# power_supply.net
KiCad netlist of a schematic drawn in Altium Designer
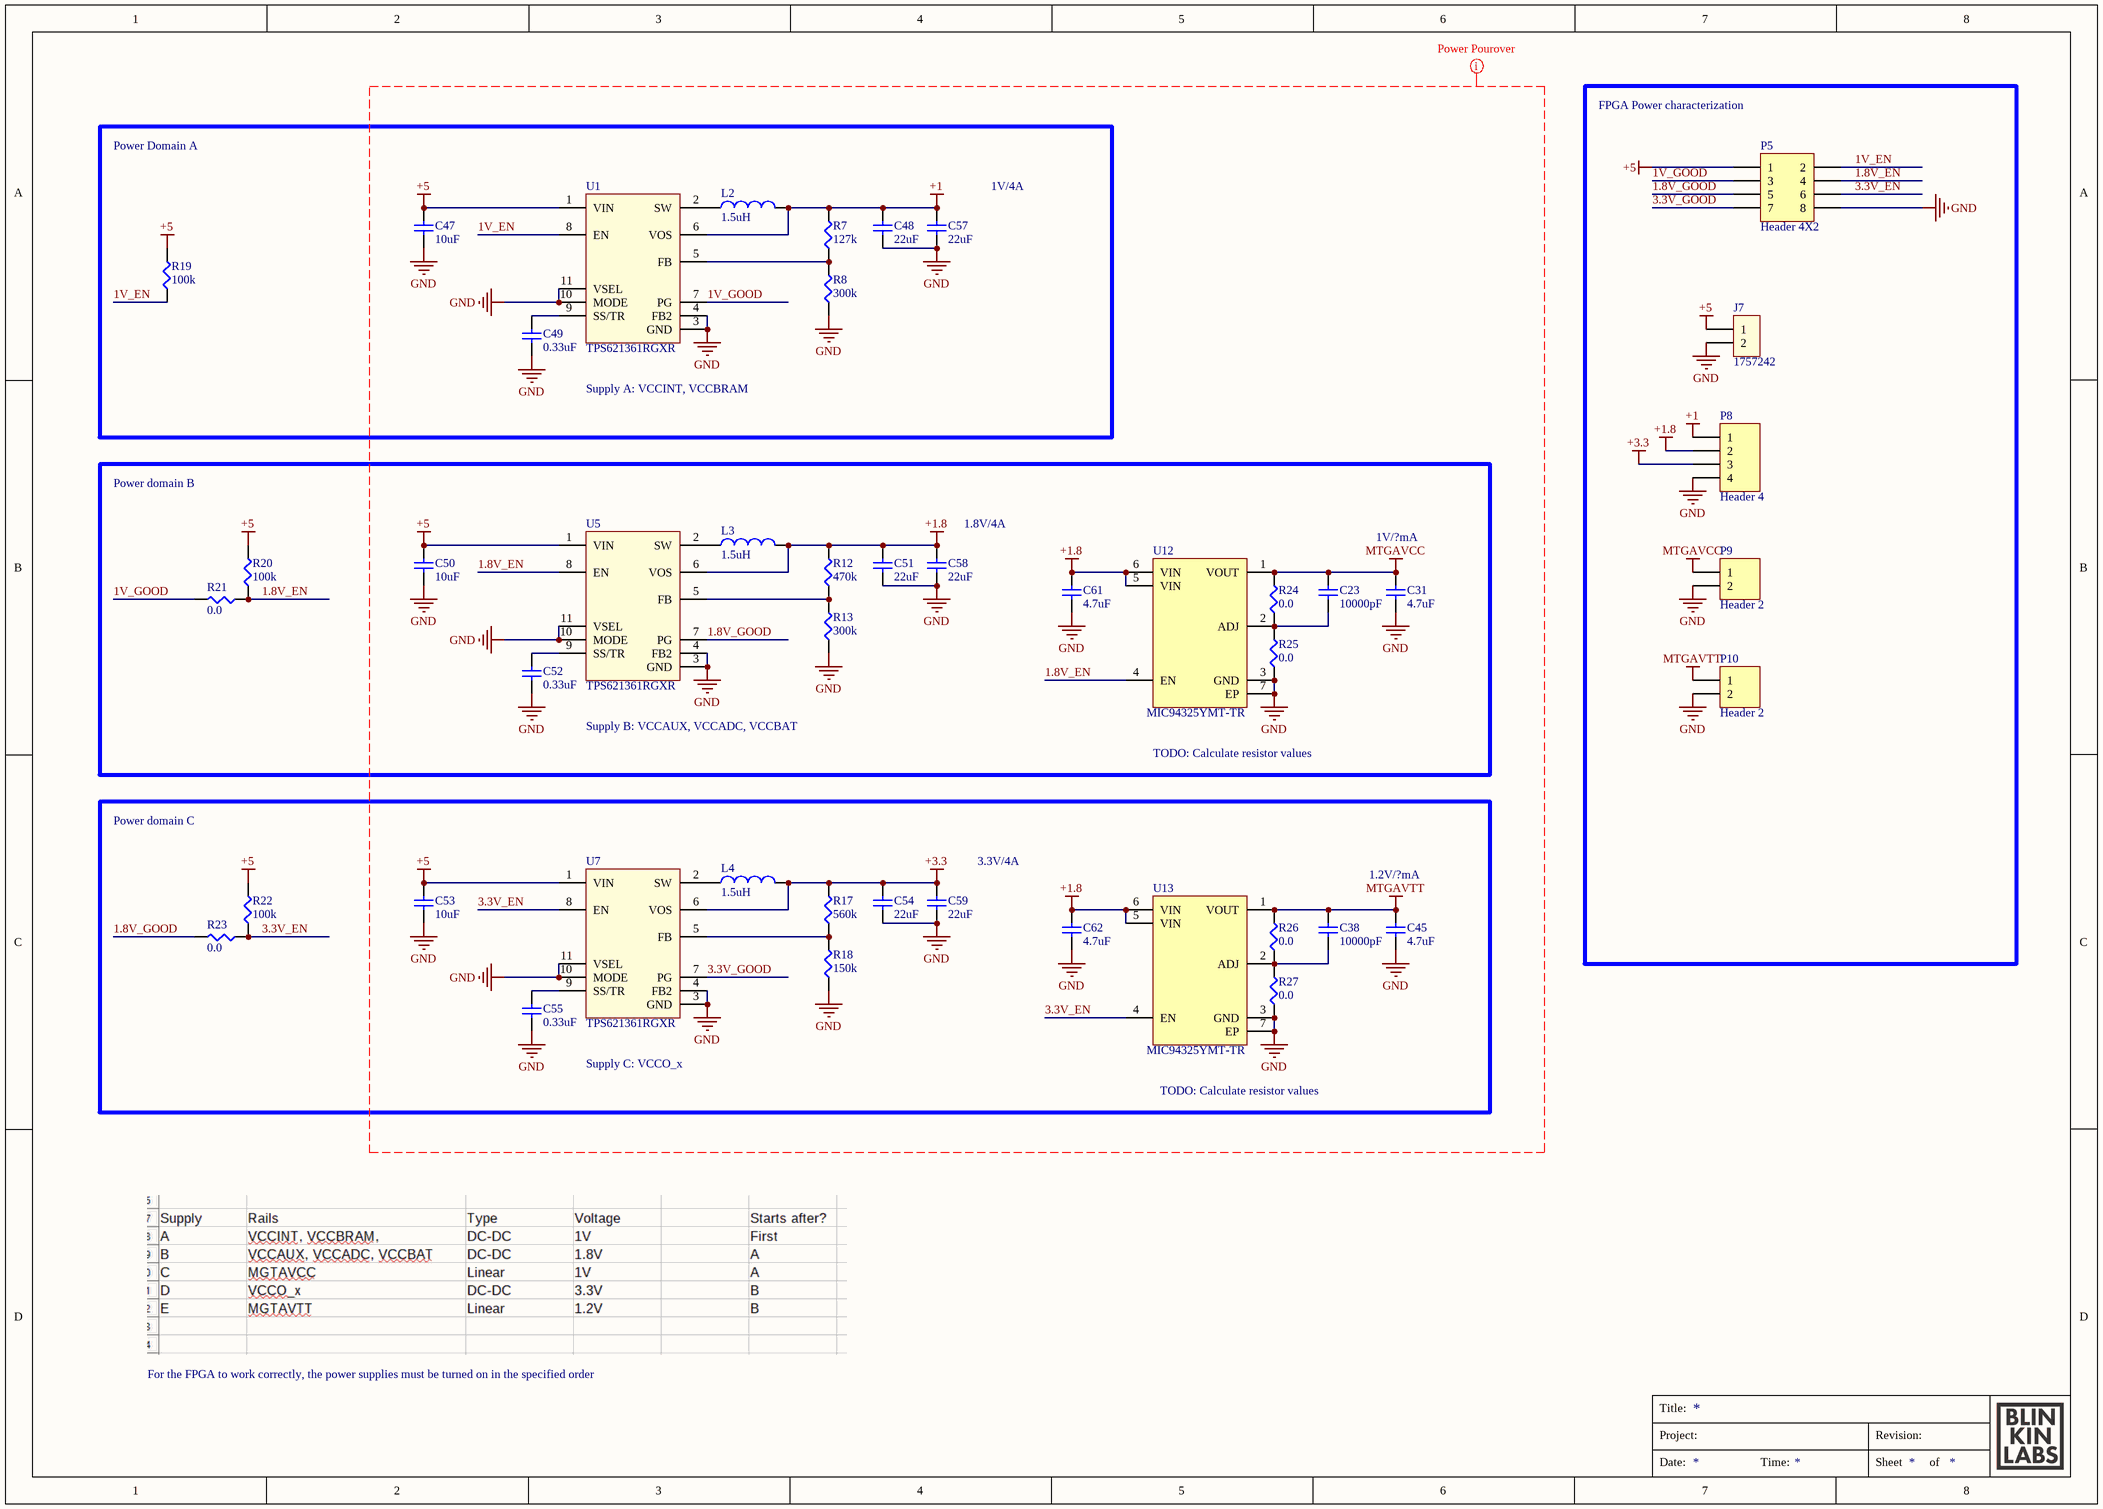
[diagram p0: power supply.SchDoc]

(export (version "E")
  (design (tool "Eeschema 10.0.6"))
  (components
    (comp (ref "C23")
      (value "10000pF")
      (footprint "CAPC1005X06L")
      (description "CAP CER 10000PF 16V X7R 0402")
      (fields
        (field (name "PARTNUMBER") "GRM155R71C103KA01D")
        (field (name "DIGI-KEY PART NUMBER") "490-1313-1-ND")
      )
      (libsource (lib "cap_murata") (part "CAPACITOR"))
    )
    (comp (ref "C31")
      (value "4.7uF")
      (footprint "CAPC1005X06L")
      (description "CAP CER 4.7UF 4V X5R 0402")
      (fields
        (field (name "PARTNUMBER") "GRM155R60G475ME47D")
        (field (name "DIGI-KEY PART NUMBER") "490-11980-1-ND")
      )
      (libsource (lib "cap_murata") (part "CAPACITOR"))
    )
    (comp (ref "C38")
      (value "10000pF")
      (footprint "CAPC1005X06L")
      (description "CAP CER 10000PF 16V X7R 0402")
      (fields
        (field (name "PARTNUMBER") "GRM155R71C103KA01D")
        (field (name "DIGI-KEY PART NUMBER") "490-1313-1-ND")
      )
      (libsource (lib "cap_murata") (part "CAPACITOR"))
    )
    (comp (ref "C45")
      (value "4.7uF")
      (footprint "CAPC1005X06L")
      (description "CAP CER 4.7UF 4V X5R 0402")
      (fields
        (field (name "PARTNUMBER") "GRM155R60G475ME47D")
        (field (name "DIGI-KEY PART NUMBER") "490-11980-1-ND")
      )
      (libsource (lib "cap_murata") (part "CAPACITOR"))
    )
    (comp (ref "C47")
      (value "10uF")
      (footprint "CAPC2012X10L")
      (description "CAP CER 10UF 10V X7R 0805")
      (fields
        (field (name "PARTNUMBER") "GRM21BR71A106KE51L")
        (field (name "DIGI-KEY PART NUMBER") "490-3905-1-ND")
      )
      (libsource (lib "cap_murata") (part "CAPACITOR"))
    )
    (comp (ref "C48")
      (value "22uF")
      (footprint "CAPC2012X10L")
      (description "CAP CER 22UF 10V X5R 0805")
      (fields
        (field (name "PARTNUMBER") "GRM219R61A226MEA0D")
        (field (name "DIGI-KEY PART NUMBER") "490-9951-1-ND")
      )
      (libsource (lib "cap_murata") (part "CAPACITOR"))
    )
    (comp (ref "C49")
      (value "0.33uF")
      (footprint "CAPC1005X06L")
      (description "CAP CER 0.33UF 6.3V X5R 0402")
      (fields
        (field (name "PARTNUMBER") "GRM155R60J334KE01D")
        (field (name "DIGI-KEY PART NUMBER") "490-3265-1-ND")
      )
      (libsource (lib "cap_murata") (part "CAPACITOR"))
    )
    (comp (ref "C50")
      (value "10uF")
      (footprint "CAPC2012X10L")
      (description "CAP CER 10UF 10V X7R 0805")
      (fields
        (field (name "PARTNUMBER") "GRM21BR71A106KE51L")
        (field (name "DIGI-KEY PART NUMBER") "490-3905-1-ND")
      )
      (libsource (lib "cap_murata") (part "CAPACITOR"))
    )
    (comp (ref "C51")
      (value "22uF")
      (footprint "CAPC2012X10L")
      (description "CAP CER 22UF 10V X5R 0805")
      (fields
        (field (name "PARTNUMBER") "GRM219R61A226MEA0D")
        (field (name "DIGI-KEY PART NUMBER") "490-9951-1-ND")
      )
      (libsource (lib "cap_murata") (part "CAPACITOR"))
    )
    (comp (ref "C52")
      (value "0.33uF")
      (footprint "CAPC1005X06L")
      (description "CAP CER 0.33UF 6.3V X5R 0402")
      (fields
        (field (name "PARTNUMBER") "GRM155R60J334KE01D")
        (field (name "DIGI-KEY PART NUMBER") "490-3265-1-ND")
      )
      (libsource (lib "cap_murata") (part "CAPACITOR"))
    )
    (comp (ref "C53")
      (value "10uF")
      (footprint "CAPC2012X10L")
      (description "CAP CER 10UF 10V X7R 0805")
      (fields
        (field (name "PARTNUMBER") "GRM21BR71A106KE51L")
        (field (name "DIGI-KEY PART NUMBER") "490-3905-1-ND")
      )
      (libsource (lib "cap_murata") (part "CAPACITOR"))
    )
    (comp (ref "C54")
      (value "22uF")
      (footprint "CAPC2012X10L")
      (description "CAP CER 22UF 10V X5R 0805")
      (fields
        (field (name "PARTNUMBER") "GRM219R61A226MEA0D")
        (field (name "DIGI-KEY PART NUMBER") "490-9951-1-ND")
      )
      (libsource (lib "cap_murata") (part "CAPACITOR"))
    )
    (comp (ref "C55")
      (value "0.33uF")
      (footprint "CAPC1005X06L")
      (description "CAP CER 0.33UF 6.3V X5R 0402")
      (fields
        (field (name "PARTNUMBER") "GRM155R60J334KE01D")
        (field (name "DIGI-KEY PART NUMBER") "490-3265-1-ND")
      )
      (libsource (lib "cap_murata") (part "CAPACITOR"))
    )
    (comp (ref "C57")
      (value "22uF")
      (footprint "CAPC2012X10L")
      (description "CAP CER 22UF 10V X5R 0805")
      (fields
        (field (name "PARTNUMBER") "GRM219R61A226MEA0D")
        (field (name "DIGI-KEY PART NUMBER") "490-9951-1-ND")
      )
      (libsource (lib "cap_murata") (part "CAPACITOR"))
    )
    (comp (ref "C58")
      (value "22uF")
      (footprint "CAPC2012X10L")
      (description "CAP CER 22UF 10V X5R 0805")
      (fields
        (field (name "PARTNUMBER") "GRM219R61A226MEA0D")
        (field (name "DIGI-KEY PART NUMBER") "490-9951-1-ND")
      )
      (libsource (lib "cap_murata") (part "CAPACITOR"))
    )
    (comp (ref "C59")
      (value "22uF")
      (footprint "CAPC2012X10L")
      (description "CAP CER 22UF 10V X5R 0805")
      (fields
        (field (name "PARTNUMBER") "GRM219R61A226MEA0D")
        (field (name "DIGI-KEY PART NUMBER") "490-9951-1-ND")
      )
      (libsource (lib "cap_murata") (part "CAPACITOR"))
    )
    (comp (ref "C61")
      (value "4.7uF")
      (footprint "CAPC1005X06L")
      (description "CAP CER 4.7UF 4V X5R 0402")
      (fields
        (field (name "PARTNUMBER") "GRM155R60G475ME47D")
        (field (name "DIGI-KEY PART NUMBER") "490-11980-1-ND")
      )
      (libsource (lib "cap_murata") (part "CAPACITOR"))
    )
    (comp (ref "C62")
      (value "4.7uF")
      (footprint "CAPC1005X06L")
      (description "CAP CER 4.7UF 4V X5R 0402")
      (fields
        (field (name "PARTNUMBER") "GRM155R60G475ME47D")
        (field (name "DIGI-KEY PART NUMBER") "490-11980-1-ND")
      )
      (libsource (lib "cap_murata") (part "CAPACITOR"))
    )
    (comp (ref "J7")
      (value "1757242")
      (footprint "1757242")
      (description "TERM BLOCK HDR 2POS 90DEG 5.08MM")
      (fields (field (name "MANUFACTURER") "Phoenix Contact") (field (name "PARTNUMBER") "1757268"))
      (libsource (lib "Blinkinlabs") (part "1757242"))
    )
    (comp (ref "L2")
      (value "1.5uH")
      (footprint "SWPA4030S")
      (description "1.5uH ±20% 3.34A 26mΩ SMD,4.0x4.0x3.0mm Power Inductors RoHS")
      (fields (field (name "PARTNUMBER") "SWPA4030S1R5NT") (field (name "LCSC PARTNUMBER") "C42100"))
      (libsource (lib "inductor_changjiang") (part "INDUCTOR"))
    )
    (comp (ref "L3")
      (value "1.5uH")
      (footprint "SWPA4030S")
      (description "1.5uH ±20% 3.34A 26mΩ SMD,4.0x4.0x3.0mm Power Inductors RoHS")
      (fields (field (name "PARTNUMBER") "SWPA4030S1R5NT") (field (name "LCSC PARTNUMBER") "C42100"))
      (libsource (lib "inductor_changjiang") (part "INDUCTOR"))
    )
    (comp (ref "L4")
      (value "1.5uH")
      (footprint "SWPA4030S")
      (description "1.5uH ±20% 3.34A 26mΩ SMD,4.0x4.0x3.0mm Power Inductors RoHS")
      (fields (field (name "PARTNUMBER") "SWPA4030S1R5NT") (field (name "LCSC PARTNUMBER") "C42100"))
      (libsource (lib "inductor_changjiang") (part "INDUCTOR"))
    )
    (comp (ref "P5")
      (value "Header 4X2")
      (footprint "HDR2X4")
      (description "Header, 4-Pin, Dual row")
      (fields (field (name "PUBLISHER") "Altium Limited"))
      (libsource (lib "Miscellaneous Connectors") (part "Header 4X2"))
    )
    (comp (ref "P8")
      (value "Header 4")
      (footprint "HDR1X4")
      (description "Header, 4-Pin")
      (fields (field (name "PUBLISHER") "Altium Limited"))
      (libsource (lib "Miscellaneous Connectors") (part "Header 4"))
    )
    (comp (ref "P9")
      (value "Header 2")
      (footprint "HDR1X2")
      (description "Header, 2-Pin")
      (fields (field (name "PUBLISHER") "Altium Limited"))
      (libsource (lib "Miscellaneous Connectors") (part "Header 2"))
    )
    (comp (ref "P10")
      (value "Header 2")
      (footprint "HDR1X2")
      (description "Header, 2-Pin")
      (fields (field (name "PUBLISHER") "Altium Limited"))
      (libsource (lib "Miscellaneous Connectors") (part "Header 2"))
    )
    (comp (ref "R7")
      (value "127k")
      (footprint "ERJ2G(0402)_L")
      (description "RES SMD 127K OHM 1% 1/10W 0402")
      (fields (field (name "PARTNUMBER") "ERJ-2RKF1273X") (field (name "DIGI-KEY PART NUMBER") "P127KLCT-ND"))
      (libsource (lib "res_panasonic_erj_xls") (part "RESISTOR"))
    )
    (comp (ref "R8")
      (value "300k")
      (footprint "ERJ2G(0402)_L")
      (description "RES SMD 300K OHM 1% 1/10W 0402")
      (fields (field (name "PARTNUMBER") "ERJ-2RKF3003X") (field (name "DIGI-KEY PART NUMBER") "P300KLCT-ND"))
      (libsource (lib "res_panasonic_erj_xls") (part "RESISTOR"))
    )
    (comp (ref "R12")
      (value "470k")
      (footprint "ERJ2G(0402)_L")
      (description "RES SMD 470K OHM 1% 1/5W 0402")
      (fields (field (name "PARTNUMBER") "ERJ-PA2F4703X") (field (name "DIGI-KEY PART NUMBER") "P17240CT-ND"))
      (libsource (lib "res_panasonic_erj_xls") (part "RESISTOR"))
    )
    (comp (ref "R13")
      (value "300k")
      (footprint "ERJ2G(0402)_L")
      (description "RES SMD 300K OHM 1% 1/10W 0402")
      (fields (field (name "PARTNUMBER") "ERJ-2RKF3003X") (field (name "DIGI-KEY PART NUMBER") "P300KLCT-ND"))
      (libsource (lib "res_panasonic_erj_xls") (part "RESISTOR"))
    )
    (comp (ref "R17")
      (value "560k")
      (footprint "ERJ2G(0402)_L")
      (description "RES SMD 560K OHM 1% 1/10W 0402")
      (fields (field (name "PARTNUMBER") "ERJ-2RKF5603X") (field (name "DIGI-KEY PART NUMBER") "P560KLCT-ND"))
      (libsource (lib "res_panasonic_erj_xls") (part "RESISTOR"))
    )
    (comp (ref "R18")
      (value "150k")
      (footprint "ERJ2G(0402)_L")
      (description "RES SMD 150K OHM 1% 1/5W 0402")
      (fields (field (name "PARTNUMBER") "ERJ-PA2F1503X") (field (name "DIGI-KEY PART NUMBER") "P17237CT-ND"))
      (libsource (lib "res_panasonic_erj_xls") (part "RESISTOR"))
    )
    (comp (ref "R19")
      (value "100k")
      (footprint "ERJ2G(0402)_L")
      (description "RES SMD 100K OHM 1% 1/5W 0402")
      (fields (field (name "PARTNUMBER") "ERJ-PA2F1003X") (field (name "DIGI-KEY PART NUMBER") "P17236CT-ND"))
      (libsource (lib "res_panasonic_erj_xls") (part "RESISTOR"))
    )
    (comp (ref "R20")
      (value "100k")
      (footprint "ERJ2G(0402)_L")
      (description "RES SMD 100K OHM 1% 1/5W 0402")
      (fields (field (name "PARTNUMBER") "ERJ-PA2F1003X") (field (name "DIGI-KEY PART NUMBER") "P17236CT-ND"))
      (libsource (lib "res_panasonic_erj_xls") (part "RESISTOR"))
    )
    (comp (ref "R21")
      (value "0.0")
      (footprint "ERJ2G(0402)_L")
      (description "RES SMD 0.0OHM JUMPER 1/10W 0402")
      (fields (field (name "PARTNUMBER") "ERJ-2GE0R00X") (field (name "DIGI-KEY PART NUMBER") "P0.0JCT-ND"))
      (libsource (lib "res_panasonic_erj_xls") (part "RESISTOR"))
    )
    (comp (ref "R22")
      (value "100k")
      (footprint "ERJ2G(0402)_L")
      (description "RES SMD 100K OHM 1% 1/5W 0402")
      (fields (field (name "PARTNUMBER") "ERJ-PA2F1003X") (field (name "DIGI-KEY PART NUMBER") "P17236CT-ND"))
      (libsource (lib "res_panasonic_erj_xls") (part "RESISTOR"))
    )
    (comp (ref "R23")
      (value "0.0")
      (footprint "ERJ2G(0402)_L")
      (description "RES SMD 0.0OHM JUMPER 1/10W 0402")
      (fields (field (name "PARTNUMBER") "ERJ-2GE0R00X") (field (name "DIGI-KEY PART NUMBER") "P0.0JCT-ND"))
      (libsource (lib "res_panasonic_erj_xls") (part "RESISTOR"))
    )
    (comp (ref "R24")
      (value "0.0")
      (footprint "ERJ2G(0402)_L")
      (description "RES SMD 0.0OHM JUMPER 1/10W 0402")
      (fields (field (name "PARTNUMBER") "ERJ-2GE0R00X") (field (name "DIGI-KEY PART NUMBER") "P0.0JCT-ND"))
      (libsource (lib "res_panasonic_erj_xls") (part "RESISTOR"))
    )
    (comp (ref "R25")
      (value "0.0")
      (footprint "ERJ2G(0402)_L")
      (description "RES SMD 0.0OHM JUMPER 1/10W 0402")
      (fields (field (name "PARTNUMBER") "ERJ-2GE0R00X") (field (name "DIGI-KEY PART NUMBER") "P0.0JCT-ND"))
      (libsource (lib "res_panasonic_erj_xls") (part "RESISTOR"))
    )
    (comp (ref "R26")
      (value "0.0")
      (footprint "ERJ2G(0402)_L")
      (description "RES SMD 0.0OHM JUMPER 1/10W 0402")
      (fields (field (name "PARTNUMBER") "ERJ-2GE0R00X") (field (name "DIGI-KEY PART NUMBER") "P0.0JCT-ND"))
      (libsource (lib "res_panasonic_erj_xls") (part "RESISTOR"))
    )
    (comp (ref "R27")
      (value "0.0")
      (footprint "ERJ2G(0402)_L")
      (description "RES SMD 0.0OHM JUMPER 1/10W 0402")
      (fields (field (name "PARTNUMBER") "ERJ-2GE0R00X") (field (name "DIGI-KEY PART NUMBER") "P0.0JCT-ND"))
      (libsource (lib "res_panasonic_erj_xls") (part "RESISTOR"))
    )
    (comp (ref "U1")
      (value "TPS621361RGXR")
      (footprint "RGX0011A")
      (description "IC REG BUCK ADJUSTABLE 4A 11VQFN")
      (fields
        (field (name "MANUFACTURER") "Texas Instruments")
        (field (name "DIGIKEY PARTNUMBER") "296-50117-2-ND")
      )
      (libsource (lib "Blinkinlabs") (part "TPS621361RGXR"))
    )
    (comp (ref "U5")
      (value "TPS621361RGXR")
      (footprint "RGX0011A")
      (description "IC REG BUCK ADJUSTABLE 4A 11VQFN")
      (fields
        (field (name "MANUFACTURER") "Texas Instruments")
        (field (name "DIGIKEY PARTNUMBER") "296-50117-2-ND")
      )
      (libsource (lib "Blinkinlabs") (part "TPS621361RGXR"))
    )
    (comp (ref "U7")
      (value "TPS621361RGXR")
      (footprint "RGX0011A")
      (description "IC REG BUCK ADJUSTABLE 4A 11VQFN")
      (fields
        (field (name "MANUFACTURER") "Texas Instruments")
        (field (name "DIGIKEY PARTNUMBER") "296-50117-2-ND")
      )
      (libsource (lib "Blinkinlabs") (part "TPS621361RGXR"))
    )
    (comp (ref "U12")
      (value "MIC94325YMT-TR")
      (footprint "QFN50P160X160X60_HS-7N")
      (description "500mA LDO with  Ripple Blocker Technology")
      (fields
        (field (name "MANUFACTURER") "Microchip Technology")
        (field (name "DIGIKEY PARTNUMBER") "576-4164-2-ND")
      )
      (libsource (lib "Blinkinlabs") (part "MIC94325YMT-TR"))
    )
    (comp (ref "U13")
      (value "MIC94325YMT-TR")
      (footprint "QFN50P160X160X60_HS-7N")
      (description "500mA LDO with  Ripple Blocker Technology")
      (fields
        (field (name "MANUFACTURER") "Microchip Technology")
        (field (name "DIGIKEY PARTNUMBER") "576-4164-2-ND")
      )
      (libsource (lib "Blinkinlabs") (part "MIC94325YMT-TR"))
    )
  )
  (nets
    (net (code "1") (name "+1") (class "Default")
      (node (ref "C48") (pin "1") (pinfunction "1_1") (pintype "passive"))
      (node (ref "C57") (pin "1") (pinfunction "1_1") (pintype "passive"))
      (node (ref "L2") (pin "2") (pinfunction "2_2") (pintype "passive"))
      (node (ref "P8") (pin "1") (pinfunction "1_1") (pintype "passive"))
      (node (ref "R7") (pin "2") (pinfunction "2_2") (pintype "passive"))
      (node (ref "U1") (pin "6") (pinfunction "VOS_6") (pintype "passive"))
    )
    (net (code "2") (name "+1.8") (class "Default")
      (node (ref "C51") (pin "1") (pinfunction "1_1") (pintype "passive"))
      (node (ref "C58") (pin "1") (pinfunction "1_1") (pintype "passive"))
      (node (ref "C61") (pin "2") (pinfunction "2_2") (pintype "passive"))
      (node (ref "C62") (pin "2") (pinfunction "2_2") (pintype "passive"))
      (node (ref "L3") (pin "2") (pinfunction "2_2") (pintype "passive"))
      (node (ref "P8") (pin "2") (pinfunction "2_2") (pintype "passive"))
      (node (ref "R12") (pin "2") (pinfunction "2_2") (pintype "passive"))
      (node (ref "U12") (pin "5") (pinfunction "VIN_5") (pintype "passive"))
      (node (ref "U12") (pin "6") (pinfunction "VIN_6") (pintype "passive"))
      (node (ref "U13") (pin "5") (pinfunction "VIN_5") (pintype "passive"))
      (node (ref "U13") (pin "6") (pinfunction "VIN_6") (pintype "passive"))
      (node (ref "U5") (pin "6") (pinfunction "VOS_6") (pintype "passive"))
    )
    (net (code "3") (name "+3.3") (class "Default")
      (node (ref "C54") (pin "1") (pinfunction "1_1") (pintype "passive"))
      (node (ref "C59") (pin "1") (pinfunction "1_1") (pintype "passive"))
      (node (ref "L4") (pin "2") (pinfunction "2_2") (pintype "passive"))
      (node (ref "P8") (pin "3") (pinfunction "3_3") (pintype "passive"))
      (node (ref "R17") (pin "2") (pinfunction "2_2") (pintype "passive"))
      (node (ref "U7") (pin "6") (pinfunction "VOS_6") (pintype "passive"))
    )
    (net (code "4") (name "+5") (class "Default")
      (node (ref "C47") (pin "1") (pinfunction "1_1") (pintype "passive"))
      (node (ref "C50") (pin "1") (pinfunction "1_1") (pintype "passive"))
      (node (ref "C53") (pin "1") (pinfunction "1_1") (pintype "passive"))
      (node (ref "J7") (pin "1") (pinfunction "1_1") (pintype "passive"))
      (node (ref "P5") (pin "1") (pinfunction "1_1") (pintype "passive"))
      (node (ref "R19") (pin "2") (pinfunction "2_2") (pintype "passive"))
      (node (ref "R20") (pin "2") (pinfunction "2_2") (pintype "passive"))
      (node (ref "R22") (pin "2") (pinfunction "2_2") (pintype "passive"))
      (node (ref "U1") (pin "1") (pinfunction "VIN_1") (pintype "passive"))
      (node (ref "U5") (pin "1") (pinfunction "VIN_1") (pintype "passive"))
      (node (ref "U7") (pin "1") (pinfunction "VIN_1") (pintype "passive"))
    )
    (net (code "5") (name "/1.8V_EN") (class "Default")
      (node (ref "P5") (pin "4") (pinfunction "4_4") (pintype "passive"))
      (node (ref "R20") (pin "1") (pinfunction "1_1") (pintype "passive"))
      (node (ref "R21") (pin "1") (pinfunction "1_1") (pintype "passive"))
      (node (ref "U12") (pin "4") (pinfunction "EN_4") (pintype "passive"))
      (node (ref "U5") (pin "8") (pinfunction "EN_8") (pintype "passive"))
    )
    (net (code "6") (name "/1.8V_GOOD") (class "Default")
      (node (ref "P5") (pin "5") (pinfunction "5_5") (pintype "passive"))
      (node (ref "R23") (pin "2") (pinfunction "2_2") (pintype "passive"))
      (node (ref "U5") (pin "7") (pinfunction "PG_7") (pintype "passive"))
    )
    (net (code "7") (name "/1V_EN") (class "Default")
      (node (ref "P5") (pin "2") (pinfunction "2_2") (pintype "passive"))
      (node (ref "R19") (pin "1") (pinfunction "1_1") (pintype "passive"))
      (node (ref "U1") (pin "8") (pinfunction "EN_8") (pintype "passive"))
    )
    (net (code "8") (name "/1V_GOOD") (class "Default")
      (node (ref "P5") (pin "3") (pinfunction "3_3") (pintype "passive"))
      (node (ref "R21") (pin "2") (pinfunction "2_2") (pintype "passive"))
      (node (ref "U1") (pin "7") (pinfunction "PG_7") (pintype "passive"))
    )
    (net (code "9") (name "/3.3V_EN") (class "Default")
      (node (ref "P5") (pin "6") (pinfunction "6_6") (pintype "passive"))
      (node (ref "R22") (pin "1") (pinfunction "1_1") (pintype "passive"))
      (node (ref "R23") (pin "1") (pinfunction "1_1") (pintype "passive"))
      (node (ref "U13") (pin "4") (pinfunction "EN_4") (pintype "passive"))
      (node (ref "U7") (pin "8") (pinfunction "EN_8") (pintype "passive"))
    )
    (net (code "10") (name "/3.3V_GOOD") (class "Default")
      (node (ref "P5") (pin "7") (pinfunction "7_7") (pintype "passive"))
      (node (ref "U7") (pin "7") (pinfunction "PG_7") (pintype "passive"))
    )
    (net (code "11") (name "GND") (class "Default")
      (node (ref "C31") (pin "1") (pinfunction "1_1") (pintype "passive"))
      (node (ref "C45") (pin "1") (pinfunction "1_1") (pintype "passive"))
      (node (ref "C47") (pin "2") (pinfunction "2_2") (pintype "passive"))
      (node (ref "C48") (pin "2") (pinfunction "2_2") (pintype "passive"))
      (node (ref "C49") (pin "2") (pinfunction "2_2") (pintype "passive"))
      (node (ref "C50") (pin "2") (pinfunction "2_2") (pintype "passive"))
      (node (ref "C51") (pin "2") (pinfunction "2_2") (pintype "passive"))
      (node (ref "C52") (pin "2") (pinfunction "2_2") (pintype "passive"))
      (node (ref "C53") (pin "2") (pinfunction "2_2") (pintype "passive"))
      (node (ref "C54") (pin "2") (pinfunction "2_2") (pintype "passive"))
      (node (ref "C55") (pin "2") (pinfunction "2_2") (pintype "passive"))
      (node (ref "C57") (pin "2") (pinfunction "2_2") (pintype "passive"))
      (node (ref "C58") (pin "2") (pinfunction "2_2") (pintype "passive"))
      (node (ref "C59") (pin "2") (pinfunction "2_2") (pintype "passive"))
      (node (ref "C61") (pin "1") (pinfunction "1_1") (pintype "passive"))
      (node (ref "C62") (pin "1") (pinfunction "1_1") (pintype "passive"))
      (node (ref "J7") (pin "2") (pinfunction "2_2") (pintype "passive"))
      (node (ref "P10") (pin "2") (pinfunction "2_2") (pintype "passive"))
      (node (ref "P5") (pin "8") (pinfunction "8_8") (pintype "passive"))
      (node (ref "P8") (pin "4") (pinfunction "4_4") (pintype "passive"))
      (node (ref "P9") (pin "2") (pinfunction "2_2") (pintype "passive"))
      (node (ref "R13") (pin "1") (pinfunction "1_1") (pintype "passive"))
      (node (ref "R18") (pin "1") (pinfunction "1_1") (pintype "passive"))
      (node (ref "R25") (pin "1") (pinfunction "1_1") (pintype "passive"))
      (node (ref "R27") (pin "1") (pinfunction "1_1") (pintype "passive"))
      (node (ref "R8") (pin "1") (pinfunction "1_1") (pintype "passive"))
      (node (ref "U1") (pin "10") (pinfunction "MODE_10") (pintype "passive"))
      (node (ref "U1") (pin "11") (pinfunction "VSEL_11") (pintype "passive"))
      (node (ref "U1") (pin "3") (pinfunction "GND_3") (pintype "passive"))
      (node (ref "U1") (pin "4") (pinfunction "FB2_4") (pintype "passive"))
      (node (ref "U12") (pin "3") (pinfunction "GND_3") (pintype "passive"))
      (node (ref "U12") (pin "7") (pinfunction "EP_7") (pintype "passive"))
      (node (ref "U13") (pin "3") (pinfunction "GND_3") (pintype "passive"))
      (node (ref "U13") (pin "7") (pinfunction "EP_7") (pintype "passive"))
      (node (ref "U5") (pin "10") (pinfunction "MODE_10") (pintype "passive"))
      (node (ref "U5") (pin "11") (pinfunction "VSEL_11") (pintype "passive"))
      (node (ref "U5") (pin "3") (pinfunction "GND_3") (pintype "passive"))
      (node (ref "U5") (pin "4") (pinfunction "FB2_4") (pintype "passive"))
      (node (ref "U7") (pin "10") (pinfunction "MODE_10") (pintype "passive"))
      (node (ref "U7") (pin "11") (pinfunction "VSEL_11") (pintype "passive"))
      (node (ref "U7") (pin "3") (pinfunction "GND_3") (pintype "passive"))
      (node (ref "U7") (pin "4") (pinfunction "FB2_4") (pintype "passive"))
    )
    (net (code "12") (name "MTGAVCC") (class "Default")
      (node (ref "C23") (pin "1") (pinfunction "1_1") (pintype "passive"))
      (node (ref "C31") (pin "2") (pinfunction "2_2") (pintype "passive"))
      (node (ref "P9") (pin "1") (pinfunction "1_1") (pintype "passive"))
      (node (ref "R24") (pin "2") (pinfunction "2_2") (pintype "passive"))
      (node (ref "U12") (pin "1") (pinfunction "VOUT_1") (pintype "passive"))
    )
    (net (code "13") (name "MTGAVTT") (class "Default")
      (node (ref "C38") (pin "1") (pinfunction "1_1") (pintype "passive"))
      (node (ref "C45") (pin "2") (pinfunction "2_2") (pintype "passive"))
      (node (ref "P10") (pin "1") (pinfunction "1_1") (pintype "passive"))
      (node (ref "R26") (pin "2") (pinfunction "2_2") (pintype "passive"))
      (node (ref "U13") (pin "1") (pinfunction "VOUT_1") (pintype "passive"))
    )
    (net (code "14") (name "Net-(U1-FB)") (class "Default")
      (node (ref "R7") (pin "1") (pinfunction "1_1") (pintype "passive"))
      (node (ref "R8") (pin "2") (pinfunction "2_2") (pintype "passive"))
      (node (ref "U1") (pin "5") (pinfunction "FB_5") (pintype "passive"))
    )
    (net (code "15") (name "Net-(U1-SS{slash}TR)") (class "Default")
      (node (ref "C49") (pin "1") (pinfunction "1_1") (pintype "passive"))
      (node (ref "U1") (pin "9") (pinfunction "SS/TR_9") (pintype "passive"))
    )
    (net (code "16") (name "Net-(U1-SW)") (class "Default")
      (node (ref "L2") (pin "1") (pinfunction "1_1") (pintype "passive"))
      (node (ref "U1") (pin "2") (pinfunction "SW_2") (pintype "passive"))
    )
    (net (code "17") (name "Net-(U5-FB)") (class "Default")
      (node (ref "R12") (pin "1") (pinfunction "1_1") (pintype "passive"))
      (node (ref "R13") (pin "2") (pinfunction "2_2") (pintype "passive"))
      (node (ref "U5") (pin "5") (pinfunction "FB_5") (pintype "passive"))
    )
    (net (code "18") (name "Net-(U5-SS{slash}TR)") (class "Default")
      (node (ref "C52") (pin "1") (pinfunction "1_1") (pintype "passive"))
      (node (ref "U5") (pin "9") (pinfunction "SS/TR_9") (pintype "passive"))
    )
    (net (code "19") (name "Net-(U5-SW)") (class "Default")
      (node (ref "L3") (pin "1") (pinfunction "1_1") (pintype "passive"))
      (node (ref "U5") (pin "2") (pinfunction "SW_2") (pintype "passive"))
    )
    (net (code "20") (name "Net-(U7-FB)") (class "Default")
      (node (ref "R17") (pin "1") (pinfunction "1_1") (pintype "passive"))
      (node (ref "R18") (pin "2") (pinfunction "2_2") (pintype "passive"))
      (node (ref "U7") (pin "5") (pinfunction "FB_5") (pintype "passive"))
    )
    (net (code "21") (name "Net-(U7-SS{slash}TR)") (class "Default")
      (node (ref "C55") (pin "1") (pinfunction "1_1") (pintype "passive"))
      (node (ref "U7") (pin "9") (pinfunction "SS/TR_9") (pintype "passive"))
    )
    (net (code "22") (name "Net-(U7-SW)") (class "Default")
      (node (ref "L4") (pin "1") (pinfunction "1_1") (pintype "passive"))
      (node (ref "U7") (pin "2") (pinfunction "SW_2") (pintype "passive"))
    )
    (net (code "23") (name "Net-(U12-ADJ)") (class "Default")
      (node (ref "C23") (pin "2") (pinfunction "2_2") (pintype "passive"))
      (node (ref "R24") (pin "1") (pinfunction "1_1") (pintype "passive"))
      (node (ref "R25") (pin "2") (pinfunction "2_2") (pintype "passive"))
      (node (ref "U12") (pin "2") (pinfunction "ADJ_2") (pintype "passive"))
    )
    (net (code "24") (name "Net-(U13-ADJ)") (class "Default")
      (node (ref "C38") (pin "2") (pinfunction "2_2") (pintype "passive"))
      (node (ref "R26") (pin "1") (pinfunction "1_1") (pintype "passive"))
      (node (ref "R27") (pin "2") (pinfunction "2_2") (pintype "passive"))
      (node (ref "U13") (pin "2") (pinfunction "ADJ_2") (pintype "passive"))
    )
  )
)
